# stm32f103vet.net
KiCad netlist of a schematic drawn in EasyEDA
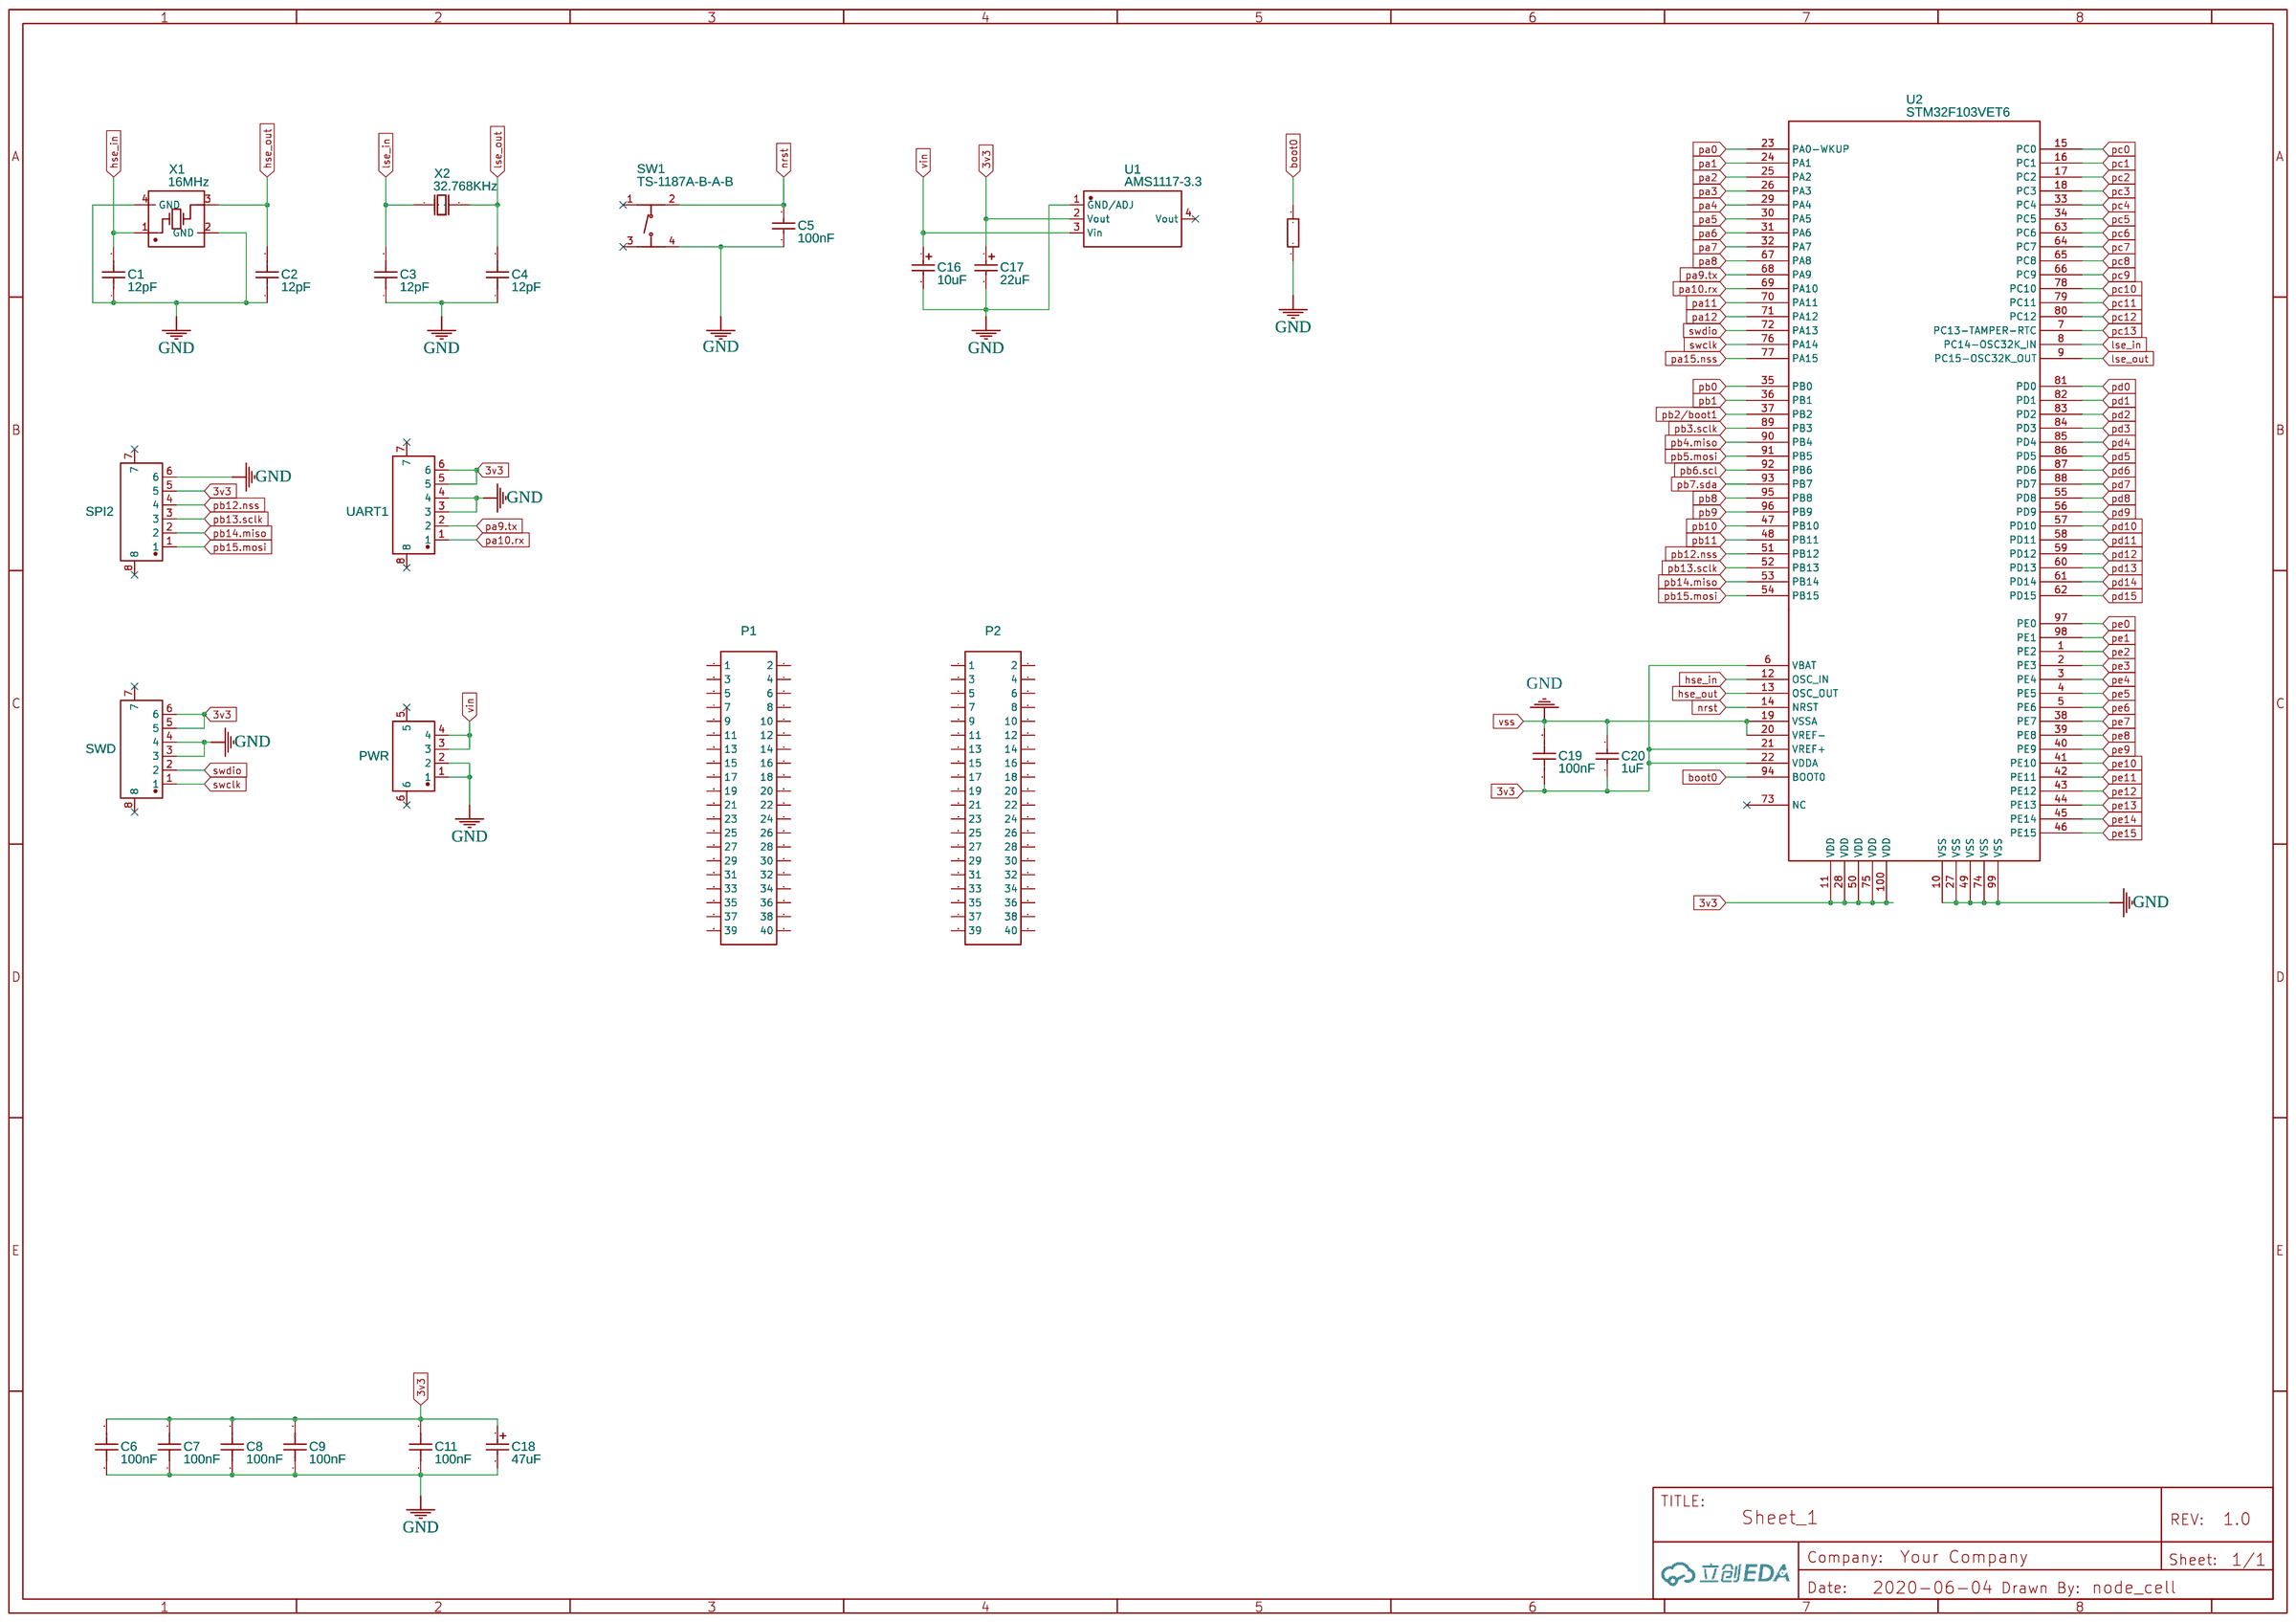
[diagram p0: schematic sheet]

(export (version "E")
  (design (tool "Eeschema 10.0.6"))
  (components
    (comp (ref "C1")
      (value "12pF")
      (fields
        (field (name "BOM_Manufacturer Part") "06035A120K4T2A")
        (field (name "BOM_Supplier Part") "C382067")
      )
      (libsource (lib "") (part "06035A120K4T2A"))
    )
    (comp (ref "C2")
      (value "12pF")
      (fields
        (field (name "BOM_Manufacturer Part") "06035A120K4T2A")
        (field (name "BOM_Supplier Part") "C382067")
      )
      (libsource (lib "") (part "06035A120K4T2A"))
    )
    (comp (ref "C3")
      (value "12pF")
      (fields
        (field (name "BOM_Manufacturer Part") "06035A120K4T2A")
        (field (name "BOM_Supplier Part") "C382067")
      )
      (libsource (lib "") (part "06035A120K4T2A"))
    )
    (comp (ref "C4")
      (value "12pF")
      (fields
        (field (name "BOM_Manufacturer Part") "06035A120K4T2A")
        (field (name "BOM_Supplier Part") "C382067")
      )
      (libsource (lib "") (part "06035A120K4T2A"))
    )
    (comp (ref "C5")
      (value "100nF")
      (fields
        (field (name "BOM_Manufacturer Part") "0603F104M500NT")
        (field (name "BOM_Supplier Part") "C42998")
      )
      (libsource (lib "") (part "0603F104M500NT"))
    )
    (comp (ref "C6")
      (value "100nF")
      (fields
        (field (name "BOM_Manufacturer Part") "C0603X104K050T")
        (field (name "BOM_Supplier Part") "C187860")
      )
      (libsource (lib "") (part "C0603X104K050T"))
    )
    (comp (ref "C7")
      (value "100nF")
      (fields
        (field (name "BOM_Manufacturer Part") "C0603X104K050T")
        (field (name "BOM_Supplier Part") "C187860")
      )
      (libsource (lib "") (part "C0603X104K050T"))
    )
    (comp (ref "C8")
      (value "100nF")
      (fields
        (field (name "BOM_Manufacturer Part") "C0603X104K050T")
        (field (name "BOM_Supplier Part") "C187860")
      )
      (libsource (lib "") (part "C0603X104K050T"))
    )
    (comp (ref "C9")
      (value "100nF")
      (fields
        (field (name "BOM_Manufacturer Part") "C0603X104K050T")
        (field (name "BOM_Supplier Part") "C187860")
      )
      (libsource (lib "") (part "C0603X104K050T"))
    )
    (comp (ref "C11")
      (value "100nF")
      (fields
        (field (name "BOM_Manufacturer Part") "C0603X104K050T")
        (field (name "BOM_Supplier Part") "C187860")
      )
      (libsource (lib "") (part "C0603X104K050T"))
    )
    (comp (ref "C16")
      (value "10uF")
      (fields
        (field (name "BOM_Manufacturer Part") "TAJB106K016RNJ")
        (field (name "BOM_Supplier Part") "C7193")
      )
      (libsource (lib "") (part "TAJB106K016RNJ"))
    )
    (comp (ref "C17")
      (value "22uF")
      (fields
        (field (name "BOM_Manufacturer Part") "TAJB226K016RNJ")
        (field (name "BOM_Supplier Part") "C8020")
      )
      (libsource (lib "") (part "TAJB226K016RNJ"))
    )
    (comp (ref "C18")
      (value "47uF")
      (fields
        (field (name "BOM_Manufacturer Part") "TAJC476K016RNJ")
        (field (name "BOM_Supplier Part") "C7219")
      )
      (libsource (lib "") (part "TAJC476K016RNJ"))
    )
    (comp (ref "C19")
      (value "100nF")
      (fields
        (field (name "BOM_Manufacturer Part") "C0603X104K050T")
        (field (name "BOM_Supplier Part") "C187860")
      )
      (libsource (lib "") (part "C0603X104K050T"))
    )
    (comp (ref "C20")
      (value "1uF")
      (fields
        (field (name "BOM_Manufacturer Part") "CL10A105KA8NNNC")
        (field (name "BOM_Supplier Part") "C5673")
      )
      (libsource (lib "") (part "CL10A105KA8NNNC"))
    )
    (comp (ref "P1")
      (value "Header-Female-2.54_2x20")
      (fields
        (field (name "BOM_Manufacturer Part") "2.54mm 2*20PFemale header")
        (field (name "BOM_Supplier Part") "C50982")
      )
      (libsource (lib "") (part "Header-Female-2.54_2x20"))
    )
    (comp (ref "P2")
      (value "Header-Female-2.54_2x20")
      (fields
        (field (name "BOM_Manufacturer Part") "2.54mm 2*20PFemale header")
        (field (name "BOM_Supplier Part") "C50982")
      )
      (libsource (lib "") (part "Header-Female-2.54_2x20"))
    )
    (comp (ref "PWR")
      (value "AFC10-S04QCC-00")
      (fields (field (name "BOM_Supplier Part") "C395301"))
      (libsource (lib "") (part "AFC10-S04QCC-00"))
    )
    (comp (ref "R2")
      (value "10K")
      (fields
        (field (name "BOM_Manufacturer Part") "0603WAF1002T5E")
        (field (name "BOM_Supplier Part") "C25804")
      )
      (libsource (lib "") (part "0603WAF1002T5E"))
    )
    (comp (ref "SPI2")
      (value "AFC10-S06QCC-00")
      (fields (field (name "BOM_Supplier Part") "C395303"))
      (libsource (lib "") (part "AFC10-S06QCC-00_1"))
    )
    (comp (ref "SW1")
      (value "TS-1187A-B-A-B")
      (fields (field (name "BOM_Supplier Part") "C318884"))
      (libsource (lib "") (part "TS-1187A-B-A-B"))
    )
    (comp (ref "SWD")
      (value "AFC10-S06QCC-00")
      (fields (field (name "BOM_Supplier Part") "C395303"))
      (libsource (lib "") (part "AFC10-S06QCC-00_2"))
    )
    (comp (ref "U1")
      (value "AMS1117-3.3")
      (fields (field (name "BOM_Supplier Part") "C6186"))
      (libsource (lib "") (part "AMS1117-3.3"))
    )
    (comp (ref "U2")
      (value "STM32F103VET6")
      (fields (field (name "BOM_Supplier Part") "C8308"))
      (libsource (lib "") (part "STM32F103VET6"))
    )
    (comp (ref "UART1")
      (value "AFC10-S06QCC-00")
      (fields (field (name "BOM_Supplier Part") "C395303"))
      (libsource (lib "") (part "AFC10-S06QCC-00"))
    )
    (comp (ref "X1")
      (value "16MHz")
      (fields
        (field (name "BOM_Manufacturer Part") "AM16000001")
        (field (name "BOM_Supplier Part") "C409359")
      )
      (libsource (lib "") (part "AM16000001"))
    )
    (comp (ref "X2")
      (value "32.768KHz")
      (fields
        (field (name "BOM_Manufacturer Part") "9H03200028")
        (field (name "BOM_Supplier Part") "C409339")
      )
      (libsource (lib "") (part "9H03200028"))
    )
  )
  (nets
    (net (code "1") (name "3v3") (class "Default")
      (node (ref "C11") (pin "2") (pinfunction "2_2") (pintype "unspecified"))
      (node (ref "C17") (pin "1") (pinfunction "1_1") (pintype "input"))
      (node (ref "C18") (pin "1") (pinfunction "1_1") (pintype "input"))
      (node (ref "C19") (pin "1") (pinfunction "1_1") (pintype "unspecified"))
      (node (ref "C20") (pin "1") (pinfunction "1_1") (pintype "input"))
      (node (ref "C6") (pin "2") (pinfunction "2_2") (pintype "unspecified"))
      (node (ref "C7") (pin "2") (pinfunction "2_2") (pintype "unspecified"))
      (node (ref "C8") (pin "2") (pinfunction "2_2") (pintype "unspecified"))
      (node (ref "C9") (pin "2") (pinfunction "2_2") (pintype "unspecified"))
      (node (ref "SPI2") (pin "5") (pinfunction "5_5") (pintype "unspecified"))
      (node (ref "SWD") (pin "5") (pinfunction "5_5") (pintype "unspecified"))
      (node (ref "SWD") (pin "6") (pinfunction "6_6") (pintype "unspecified"))
      (node (ref "U1") (pin "2") (pinfunction "Vout_2") (pintype "unspecified"))
      (node (ref "U2") (pin "100") (pinfunction "VDD_100") (pintype "unspecified"))
      (node (ref "U2") (pin "11") (pinfunction "VDD_11") (pintype "unspecified"))
      (node (ref "U2") (pin "21") (pinfunction "VREF+_21") (pintype "unspecified"))
      (node (ref "U2") (pin "22") (pinfunction "VDDA_22") (pintype "unspecified"))
      (node (ref "U2") (pin "28") (pinfunction "VDD_28") (pintype "unspecified"))
      (node (ref "U2") (pin "50") (pinfunction "VDD_50") (pintype "unspecified"))
      (node (ref "U2") (pin "6") (pinfunction "VBAT_6") (pintype "unspecified"))
      (node (ref "U2") (pin "75") (pinfunction "VDD_75") (pintype "unspecified"))
      (node (ref "UART1") (pin "5") (pinfunction "5_5") (pintype "unspecified"))
      (node (ref "UART1") (pin "6") (pinfunction "6_6") (pintype "unspecified"))
    )
    (net (code "2") (name "boot0") (class "Default")
      (node (ref "R2") (pin "2") (pinfunction "2_2") (pintype "input"))
      (node (ref "U2") (pin "94") (pinfunction "BOOT0_94") (pintype "unspecified"))
    )
    (net (code "3") (name "hse_in") (class "Default")
      (node (ref "C1") (pin "2") (pinfunction "2_2") (pintype "unspecified"))
      (node (ref "U2") (pin "12") (pinfunction "OSC_IN_12") (pintype "unspecified"))
      (node (ref "X1") (pin "1") (pinfunction "1_1") (pintype "input"))
    )
    (net (code "4") (name "hse_out") (class "Default")
      (node (ref "C2") (pin "2") (pinfunction "2_2") (pintype "unspecified"))
      (node (ref "U2") (pin "13") (pinfunction "OSC_OUT_13") (pintype "unspecified"))
      (node (ref "X1") (pin "3") (pinfunction "3_3") (pintype "input"))
    )
    (net (code "5") (name "lse_in") (class "Default")
      (node (ref "C3") (pin "2") (pinfunction "2_2") (pintype "unspecified"))
      (node (ref "U2") (pin "8") (pinfunction "PC14-OSC32K_IN_8") (pintype "unspecified"))
      (node (ref "X2") (pin "1") (pinfunction "OSC1_1") (pintype "input"))
    )
    (net (code "6") (name "lse_out") (class "Default")
      (node (ref "C4") (pin "2") (pinfunction "2_2") (pintype "unspecified"))
      (node (ref "U2") (pin "9") (pinfunction "PC15-OSC32K_OUT_9") (pintype "unspecified"))
      (node (ref "X2") (pin "2") (pinfunction "OSC2_2") (pintype "input"))
    )
    (net (code "7") (name "nrst") (class "Default")
      (node (ref "C5") (pin "2") (pinfunction "2_2") (pintype "input"))
      (node (ref "SW1") (pin "2") (pinfunction "B_2") (pintype "unspecified"))
      (node (ref "U2") (pin "14") (pinfunction "NRST_14") (pintype "unspecified"))
    )
    (net (code "8") (name "pa0") (class "Default")
      (node (ref "U2") (pin "23") (pinfunction "PA0-WKUP_23") (pintype "unspecified"))
    )
    (net (code "9") (name "pa1") (class "Default")
      (node (ref "U2") (pin "24") (pinfunction "PA1_24") (pintype "unspecified"))
    )
    (net (code "10") (name "pa2") (class "Default")
      (node (ref "U2") (pin "25") (pinfunction "PA2_25") (pintype "unspecified"))
    )
    (net (code "11") (name "pa3") (class "Default")
      (node (ref "U2") (pin "26") (pinfunction "PA3_26") (pintype "unspecified"))
    )
    (net (code "12") (name "pa4") (class "Default")
      (node (ref "U2") (pin "29") (pinfunction "PA4_29") (pintype "unspecified"))
    )
    (net (code "13") (name "pa5") (class "Default")
      (node (ref "U2") (pin "30") (pinfunction "PA5_30") (pintype "unspecified"))
    )
    (net (code "14") (name "pa6") (class "Default")
      (node (ref "U2") (pin "31") (pinfunction "PA6_31") (pintype "unspecified"))
    )
    (net (code "15") (name "pa7") (class "Default")
      (node (ref "U2") (pin "32") (pinfunction "PA7_32") (pintype "unspecified"))
    )
    (net (code "16") (name "pa8") (class "Default")
      (node (ref "U2") (pin "67") (pinfunction "PA8_67") (pintype "unspecified"))
    )
    (net (code "17") (name "pa9.tx") (class "Default")
      (node (ref "U2") (pin "68") (pinfunction "PA9_68") (pintype "unspecified"))
      (node (ref "UART1") (pin "2") (pinfunction "2_2") (pintype "unspecified"))
    )
    (net (code "18") (name "pa10.rx") (class "Default")
      (node (ref "U2") (pin "69") (pinfunction "PA10_69") (pintype "unspecified"))
      (node (ref "UART1") (pin "1") (pinfunction "1_1") (pintype "unspecified"))
    )
    (net (code "19") (name "pa11") (class "Default")
      (node (ref "U2") (pin "70") (pinfunction "PA11_70") (pintype "unspecified"))
    )
    (net (code "20") (name "pa12") (class "Default")
      (node (ref "U2") (pin "71") (pinfunction "PA12_71") (pintype "unspecified"))
    )
    (net (code "21") (name "pa15.nss") (class "Default")
      (node (ref "U2") (pin "77") (pinfunction "PA15_77") (pintype "unspecified"))
    )
    (net (code "22") (name "pb0") (class "Default")
      (node (ref "U2") (pin "35") (pinfunction "PB0_35") (pintype "unspecified"))
    )
    (net (code "23") (name "pb1") (class "Default")
      (node (ref "U2") (pin "36") (pinfunction "PB1_36") (pintype "unspecified"))
    )
    (net (code "24") (name "pb2{slash}boot1") (class "Default")
      (node (ref "U2") (pin "37") (pinfunction "PB2_37") (pintype "unspecified"))
    )
    (net (code "25") (name "pb3.sclk") (class "Default")
      (node (ref "U2") (pin "89") (pinfunction "PB3_89") (pintype "unspecified"))
    )
    (net (code "26") (name "pb4.miso") (class "Default")
      (node (ref "U2") (pin "90") (pinfunction "PB4_90") (pintype "unspecified"))
    )
    (net (code "27") (name "pb5.mosi") (class "Default")
      (node (ref "U2") (pin "91") (pinfunction "PB5_91") (pintype "unspecified"))
    )
    (net (code "28") (name "pb6.scl") (class "Default")
      (node (ref "U2") (pin "92") (pinfunction "PB6_92") (pintype "unspecified"))
    )
    (net (code "29") (name "pb7.sda") (class "Default")
      (node (ref "U2") (pin "93") (pinfunction "PB7_93") (pintype "unspecified"))
    )
    (net (code "30") (name "pb8") (class "Default")
      (node (ref "U2") (pin "95") (pinfunction "PB8_95") (pintype "unspecified"))
    )
    (net (code "31") (name "pb9") (class "Default")
      (node (ref "U2") (pin "96") (pinfunction "PB9_96") (pintype "unspecified"))
    )
    (net (code "32") (name "pb10") (class "Default")
      (node (ref "U2") (pin "47") (pinfunction "PB10_47") (pintype "unspecified"))
    )
    (net (code "33") (name "pb11") (class "Default")
      (node (ref "U2") (pin "48") (pinfunction "PB11_48") (pintype "unspecified"))
    )
    (net (code "34") (name "pb12.nss") (class "Default")
      (node (ref "SPI2") (pin "4") (pinfunction "4_4") (pintype "unspecified"))
      (node (ref "U2") (pin "51") (pinfunction "PB12_51") (pintype "unspecified"))
    )
    (net (code "35") (name "pb13.sclk") (class "Default")
      (node (ref "SPI2") (pin "3") (pinfunction "3_3") (pintype "unspecified"))
      (node (ref "U2") (pin "52") (pinfunction "PB13_52") (pintype "unspecified"))
    )
    (net (code "36") (name "pb14.miso") (class "Default")
      (node (ref "SPI2") (pin "2") (pinfunction "2_2") (pintype "unspecified"))
      (node (ref "U2") (pin "53") (pinfunction "PB14_53") (pintype "unspecified"))
    )
    (net (code "37") (name "pb15.mosi") (class "Default")
      (node (ref "SPI2") (pin "1") (pinfunction "1_1") (pintype "unspecified"))
      (node (ref "U2") (pin "54") (pinfunction "PB15_54") (pintype "unspecified"))
    )
    (net (code "38") (name "pc0") (class "Default")
      (node (ref "U2") (pin "15") (pinfunction "PC0_15") (pintype "unspecified"))
    )
    (net (code "39") (name "pc1") (class "Default")
      (node (ref "U2") (pin "16") (pinfunction "PC1_16") (pintype "unspecified"))
    )
    (net (code "40") (name "pc2") (class "Default")
      (node (ref "U2") (pin "17") (pinfunction "PC2_17") (pintype "unspecified"))
    )
    (net (code "41") (name "pc3") (class "Default")
      (node (ref "U2") (pin "18") (pinfunction "PC3_18") (pintype "unspecified"))
    )
    (net (code "42") (name "pc4") (class "Default")
      (node (ref "U2") (pin "33") (pinfunction "PC4_33") (pintype "unspecified"))
    )
    (net (code "43") (name "pc5") (class "Default")
      (node (ref "U2") (pin "34") (pinfunction "PC5_34") (pintype "unspecified"))
    )
    (net (code "44") (name "pc6") (class "Default")
      (node (ref "U2") (pin "63") (pinfunction "PC6_63") (pintype "unspecified"))
    )
    (net (code "45") (name "pc7") (class "Default")
      (node (ref "U2") (pin "64") (pinfunction "PC7_64") (pintype "unspecified"))
    )
    (net (code "46") (name "pc8") (class "Default")
      (node (ref "U2") (pin "65") (pinfunction "PC8_65") (pintype "unspecified"))
    )
    (net (code "47") (name "pc9") (class "Default")
      (node (ref "U2") (pin "66") (pinfunction "PC9_66") (pintype "unspecified"))
    )
    (net (code "48") (name "pc10") (class "Default")
      (node (ref "U2") (pin "78") (pinfunction "PC10_78") (pintype "unspecified"))
    )
    (net (code "49") (name "pc11") (class "Default")
      (node (ref "U2") (pin "79") (pinfunction "PC11_79") (pintype "unspecified"))
    )
    (net (code "50") (name "pc12") (class "Default")
      (node (ref "U2") (pin "80") (pinfunction "PC12_80") (pintype "unspecified"))
    )
    (net (code "51") (name "pc13") (class "Default")
      (node (ref "U2") (pin "7") (pinfunction "PC13-TAMPER-RTC_7") (pintype "unspecified"))
    )
    (net (code "52") (name "pd0") (class "Default")
      (node (ref "U2") (pin "81") (pinfunction "PD0_81") (pintype "unspecified"))
    )
    (net (code "53") (name "pd1") (class "Default")
      (node (ref "U2") (pin "82") (pinfunction "PD1_82") (pintype "unspecified"))
    )
    (net (code "54") (name "pd2") (class "Default")
      (node (ref "U2") (pin "83") (pinfunction "PD2_83") (pintype "unspecified"))
    )
    (net (code "55") (name "pd3") (class "Default")
      (node (ref "U2") (pin "84") (pinfunction "PD3_84") (pintype "unspecified"))
    )
    (net (code "56") (name "pd4") (class "Default")
      (node (ref "U2") (pin "85") (pinfunction "PD4_85") (pintype "unspecified"))
    )
    (net (code "57") (name "pd5") (class "Default")
      (node (ref "U2") (pin "86") (pinfunction "PD5_86") (pintype "unspecified"))
    )
    (net (code "58") (name "pd6") (class "Default")
      (node (ref "U2") (pin "87") (pinfunction "PD6_87") (pintype "unspecified"))
    )
    (net (code "59") (name "pd7") (class "Default")
      (node (ref "U2") (pin "88") (pinfunction "PD7_88") (pintype "unspecified"))
    )
    (net (code "60") (name "pd8") (class "Default")
      (node (ref "U2") (pin "55") (pinfunction "PD8_55") (pintype "unspecified"))
    )
    (net (code "61") (name "pd9") (class "Default")
      (node (ref "U2") (pin "56") (pinfunction "PD9_56") (pintype "unspecified"))
    )
    (net (code "62") (name "pd10") (class "Default")
      (node (ref "U2") (pin "57") (pinfunction "PD10_57") (pintype "unspecified"))
    )
    (net (code "63") (name "pd11") (class "Default")
      (node (ref "U2") (pin "58") (pinfunction "PD11_58") (pintype "unspecified"))
    )
    (net (code "64") (name "pd12") (class "Default")
      (node (ref "U2") (pin "59") (pinfunction "PD12_59") (pintype "unspecified"))
    )
    (net (code "65") (name "pd13") (class "Default")
      (node (ref "U2") (pin "60") (pinfunction "PD13_60") (pintype "unspecified"))
    )
    (net (code "66") (name "pd14") (class "Default")
      (node (ref "U2") (pin "61") (pinfunction "PD14_61") (pintype "unspecified"))
    )
    (net (code "67") (name "pd15") (class "Default")
      (node (ref "U2") (pin "62") (pinfunction "PD15_62") (pintype "unspecified"))
    )
    (net (code "68") (name "pe0") (class "Default")
      (node (ref "U2") (pin "97") (pinfunction "PE0_97") (pintype "unspecified"))
    )
    (net (code "69") (name "pe1") (class "Default")
      (node (ref "U2") (pin "98") (pinfunction "PE1_98") (pintype "unspecified"))
    )
    (net (code "70") (name "pe2") (class "Default")
      (node (ref "U2") (pin "1") (pinfunction "PE2_1") (pintype "unspecified"))
    )
    (net (code "71") (name "pe3") (class "Default")
      (node (ref "U2") (pin "2") (pinfunction "PE3_2") (pintype "unspecified"))
    )
    (net (code "72") (name "pe4") (class "Default")
      (node (ref "U2") (pin "3") (pinfunction "PE4_3") (pintype "unspecified"))
    )
    (net (code "73") (name "pe5") (class "Default")
      (node (ref "U2") (pin "4") (pinfunction "PE5_4") (pintype "unspecified"))
    )
    (net (code "74") (name "pe6") (class "Default")
      (node (ref "U2") (pin "5") (pinfunction "PE6_5") (pintype "unspecified"))
    )
    (net (code "75") (name "pe7") (class "Default")
      (node (ref "U2") (pin "38") (pinfunction "PE7_38") (pintype "unspecified"))
    )
    (net (code "76") (name "pe8") (class "Default")
      (node (ref "U2") (pin "39") (pinfunction "PE8_39") (pintype "unspecified"))
    )
    (net (code "77") (name "pe9") (class "Default")
      (node (ref "U2") (pin "40") (pinfunction "PE9_40") (pintype "unspecified"))
    )
    (net (code "78") (name "pe10") (class "Default")
      (node (ref "U2") (pin "41") (pinfunction "PE10_41") (pintype "unspecified"))
    )
    (net (code "79") (name "pe11") (class "Default")
      (node (ref "U2") (pin "42") (pinfunction "PE11_42") (pintype "unspecified"))
    )
    (net (code "80") (name "pe12") (class "Default")
      (node (ref "U2") (pin "43") (pinfunction "PE12_43") (pintype "unspecified"))
    )
    (net (code "81") (name "pe13") (class "Default")
      (node (ref "U2") (pin "44") (pinfunction "PE13_44") (pintype "unspecified"))
    )
    (net (code "82") (name "pe14") (class "Default")
      (node (ref "U2") (pin "45") (pinfunction "PE14_45") (pintype "unspecified"))
    )
    (net (code "83") (name "pe15") (class "Default")
      (node (ref "U2") (pin "46") (pinfunction "PE15_46") (pintype "unspecified"))
    )
    (net (code "84") (name "swclk") (class "Default")
      (node (ref "SWD") (pin "1") (pinfunction "1_1") (pintype "unspecified"))
      (node (ref "U2") (pin "76") (pinfunction "PA14_76") (pintype "unspecified"))
    )
    (net (code "85") (name "swdio") (class "Default")
      (node (ref "SWD") (pin "2") (pinfunction "2_2") (pintype "unspecified"))
      (node (ref "U2") (pin "72") (pinfunction "PA13_72") (pintype "unspecified"))
    )
    (net (code "86") (name "unconnected-(P1-Pad1)") (class "Default")
      (node (ref "P1") (pin "1") (pinfunction "1_1") (pintype "input"))
    )
    (net (code "87") (name "unconnected-(P1-Pad2)") (class "Default")
      (node (ref "P1") (pin "2") (pinfunction "2_2") (pintype "input"))
    )
    (net (code "88") (name "unconnected-(P1-Pad3)") (class "Default")
      (node (ref "P1") (pin "3") (pinfunction "3_3") (pintype "input"))
    )
    (net (code "89") (name "unconnected-(P1-Pad4)") (class "Default")
      (node (ref "P1") (pin "4") (pinfunction "4_4") (pintype "input"))
    )
    (net (code "90") (name "unconnected-(P1-Pad5)") (class "Default")
      (node (ref "P1") (pin "5") (pinfunction "5_5") (pintype "input"))
    )
    (net (code "91") (name "unconnected-(P1-Pad6)") (class "Default")
      (node (ref "P1") (pin "6") (pinfunction "6_6") (pintype "input"))
    )
    (net (code "92") (name "unconnected-(P1-Pad7)") (class "Default")
      (node (ref "P1") (pin "7") (pinfunction "7_7") (pintype "input"))
    )
    (net (code "93") (name "unconnected-(P1-Pad8)") (class "Default")
      (node (ref "P1") (pin "8") (pinfunction "8_8") (pintype "input"))
    )
    (net (code "94") (name "unconnected-(P1-Pad9)") (class "Default")
      (node (ref "P1") (pin "9") (pinfunction "9_9") (pintype "input"))
    )
    (net (code "95") (name "unconnected-(P1-Pad10)") (class "Default")
      (node (ref "P1") (pin "10") (pinfunction "10_10") (pintype "input"))
    )
    (net (code "96") (name "unconnected-(P1-Pad11)") (class "Default")
      (node (ref "P1") (pin "11") (pinfunction "11_11") (pintype "input"))
    )
    (net (code "97") (name "unconnected-(P1-Pad12)") (class "Default")
      (node (ref "P1") (pin "12") (pinfunction "12_12") (pintype "input"))
    )
    (net (code "98") (name "unconnected-(P1-Pad13)") (class "Default")
      (node (ref "P1") (pin "13") (pinfunction "13_13") (pintype "input"))
    )
    (net (code "99") (name "unconnected-(P1-Pad14)") (class "Default")
      (node (ref "P1") (pin "14") (pinfunction "14_14") (pintype "input"))
    )
    (net (code "100") (name "unconnected-(P1-Pad15)") (class "Default")
      (node (ref "P1") (pin "15") (pinfunction "15_15") (pintype "input"))
    )
    (net (code "101") (name "unconnected-(P1-Pad16)") (class "Default")
      (node (ref "P1") (pin "16") (pinfunction "16_16") (pintype "input"))
    )
    (net (code "102") (name "unconnected-(P1-Pad17)") (class "Default")
      (node (ref "P1") (pin "17") (pinfunction "17_17") (pintype "input"))
    )
    (net (code "103") (name "unconnected-(P1-Pad18)") (class "Default")
      (node (ref "P1") (pin "18") (pinfunction "18_18") (pintype "input"))
    )
    (net (code "104") (name "unconnected-(P1-Pad19)") (class "Default")
      (node (ref "P1") (pin "19") (pinfunction "19_19") (pintype "input"))
    )
    (net (code "105") (name "unconnected-(P1-Pad20)") (class "Default")
      (node (ref "P1") (pin "20") (pinfunction "20_20") (pintype "input"))
    )
    (net (code "106") (name "unconnected-(P1-Pad21)") (class "Default")
      (node (ref "P1") (pin "21") (pinfunction "21_21") (pintype "input"))
    )
    (net (code "107") (name "unconnected-(P1-Pad22)") (class "Default")
      (node (ref "P1") (pin "22") (pinfunction "22_22") (pintype "input"))
    )
    (net (code "108") (name "unconnected-(P1-Pad23)") (class "Default")
      (node (ref "P1") (pin "23") (pinfunction "23_23") (pintype "input"))
    )
    (net (code "109") (name "unconnected-(P1-Pad24)") (class "Default")
      (node (ref "P1") (pin "24") (pinfunction "24_24") (pintype "input"))
    )
    (net (code "110") (name "unconnected-(P1-Pad25)") (class "Default")
      (node (ref "P1") (pin "25") (pinfunction "25_25") (pintype "input"))
    )
    (net (code "111") (name "unconnected-(P1-Pad26)") (class "Default")
      (node (ref "P1") (pin "26") (pinfunction "26_26") (pintype "input"))
    )
    (net (code "112") (name "unconnected-(P1-Pad27)") (class "Default")
      (node (ref "P1") (pin "27") (pinfunction "27_27") (pintype "input"))
    )
    (net (code "113") (name "unconnected-(P1-Pad28)") (class "Default")
      (node (ref "P1") (pin "28") (pinfunction "28_28") (pintype "input"))
    )
    (net (code "114") (name "unconnected-(P1-Pad29)") (class "Default")
      (node (ref "P1") (pin "29") (pinfunction "29_29") (pintype "input"))
    )
    (net (code "115") (name "unconnected-(P1-Pad30)") (class "Default")
      (node (ref "P1") (pin "30") (pinfunction "30_30") (pintype "input"))
    )
    (net (code "116") (name "unconnected-(P1-Pad31)") (class "Default")
      (node (ref "P1") (pin "31") (pinfunction "31_31") (pintype "input"))
    )
    (net (code "117") (name "unconnected-(P1-Pad32)") (class "Default")
      (node (ref "P1") (pin "32") (pinfunction "32_32") (pintype "input"))
    )
    (net (code "118") (name "unconnected-(P1-Pad33)") (class "Default")
      (node (ref "P1") (pin "33") (pinfunction "33_33") (pintype "input"))
    )
    (net (code "119") (name "unconnected-(P1-Pad34)") (class "Default")
      (node (ref "P1") (pin "34") (pinfunction "34_34") (pintype "input"))
    )
    (net (code "120") (name "unconnected-(P1-Pad35)") (class "Default")
      (node (ref "P1") (pin "35") (pinfunction "35_35") (pintype "input"))
    )
    (net (code "121") (name "unconnected-(P1-Pad36)") (class "Default")
      (node (ref "P1") (pin "36") (pinfunction "36_36") (pintype "input"))
    )
    (net (code "122") (name "unconnected-(P1-Pad37)") (class "Default")
      (node (ref "P1") (pin "37") (pinfunction "37_37") (pintype "input"))
    )
    (net (code "123") (name "unconnected-(P1-Pad38)") (class "Default")
      (node (ref "P1") (pin "38") (pinfunction "38_38") (pintype "input"))
    )
    (net (code "124") (name "unconnected-(P1-Pad39)") (class "Default")
      (node (ref "P1") (pin "39") (pinfunction "39_39") (pintype "input"))
    )
    (net (code "125") (name "unconnected-(P1-Pad40)") (class "Default")
      (node (ref "P1") (pin "40") (pinfunction "40_40") (pintype "input"))
    )
    (net (code "126") (name "unconnected-(P2-Pad1)") (class "Default")
      (node (ref "P2") (pin "1") (pinfunction "1_1") (pintype "input"))
    )
    (net (code "127") (name "unconnected-(P2-Pad2)") (class "Default")
      (node (ref "P2") (pin "2") (pinfunction "2_2") (pintype "input"))
    )
    (net (code "128") (name "unconnected-(P2-Pad3)") (class "Default")
      (node (ref "P2") (pin "3") (pinfunction "3_3") (pintype "input"))
    )
    (net (code "129") (name "unconnected-(P2-Pad4)") (class "Default")
      (node (ref "P2") (pin "4") (pinfunction "4_4") (pintype "input"))
    )
    (net (code "130") (name "unconnected-(P2-Pad5)") (class "Default")
      (node (ref "P2") (pin "5") (pinfunction "5_5") (pintype "input"))
    )
    (net (code "131") (name "unconnected-(P2-Pad6)") (class "Default")
      (node (ref "P2") (pin "6") (pinfunction "6_6") (pintype "input"))
    )
    (net (code "132") (name "unconnected-(P2-Pad7)") (class "Default")
      (node (ref "P2") (pin "7") (pinfunction "7_7") (pintype "input"))
    )
    (net (code "133") (name "unconnected-(P2-Pad8)") (class "Default")
      (node (ref "P2") (pin "8") (pinfunction "8_8") (pintype "input"))
    )
    (net (code "134") (name "unconnected-(P2-Pad9)") (class "Default")
      (node (ref "P2") (pin "9") (pinfunction "9_9") (pintype "input"))
    )
    (net (code "135") (name "unconnected-(P2-Pad10)") (class "Default")
      (node (ref "P2") (pin "10") (pinfunction "10_10") (pintype "input"))
    )
    (net (code "136") (name "unconnected-(P2-Pad11)") (class "Default")
      (node (ref "P2") (pin "11") (pinfunction "11_11") (pintype "input"))
    )
    (net (code "137") (name "unconnected-(P2-Pad12)") (class "Default")
      (node (ref "P2") (pin "12") (pinfunction "12_12") (pintype "input"))
    )
    (net (code "138") (name "unconnected-(P2-Pad13)") (class "Default")
      (node (ref "P2") (pin "13") (pinfunction "13_13") (pintype "input"))
    )
    (net (code "139") (name "unconnected-(P2-Pad14)") (class "Default")
      (node (ref "P2") (pin "14") (pinfunction "14_14") (pintype "input"))
    )
    (net (code "140") (name "unconnected-(P2-Pad15)") (class "Default")
      (node (ref "P2") (pin "15") (pinfunction "15_15") (pintype "input"))
    )
    (net (code "141") (name "unconnected-(P2-Pad16)") (class "Default")
      (node (ref "P2") (pin "16") (pinfunction "16_16") (pintype "input"))
    )
    (net (code "142") (name "unconnected-(P2-Pad17)") (class "Default")
      (node (ref "P2") (pin "17") (pinfunction "17_17") (pintype "input"))
    )
    (net (code "143") (name "unconnected-(P2-Pad18)") (class "Default")
      (node (ref "P2") (pin "18") (pinfunction "18_18") (pintype "input"))
    )
    (net (code "144") (name "unconnected-(P2-Pad19)") (class "Default")
      (node (ref "P2") (pin "19") (pinfunction "19_19") (pintype "input"))
    )
    (net (code "145") (name "unconnected-(P2-Pad20)") (class "Default")
      (node (ref "P2") (pin "20") (pinfunction "20_20") (pintype "input"))
    )
    (net (code "146") (name "unconnected-(P2-Pad21)") (class "Default")
      (node (ref "P2") (pin "21") (pinfunction "21_21") (pintype "input"))
    )
    (net (code "147") (name "unconnected-(P2-Pad22)") (class "Default")
      (node (ref "P2") (pin "22") (pinfunction "22_22") (pintype "input"))
    )
    (net (code "148") (name "unconnected-(P2-Pad23)") (class "Default")
      (node (ref "P2") (pin "23") (pinfunction "23_23") (pintype "input"))
    )
    (net (code "149") (name "unconnected-(P2-Pad24)") (class "Default")
      (node (ref "P2") (pin "24") (pinfunction "24_24") (pintype "input"))
    )
    (net (code "150") (name "unconnected-(P2-Pad25)") (class "Default")
      (node (ref "P2") (pin "25") (pinfunction "25_25") (pintype "input"))
    )
    (net (code "151") (name "unconnected-(P2-Pad26)") (class "Default")
      (node (ref "P2") (pin "26") (pinfunction "26_26") (pintype "input"))
    )
    (net (code "152") (name "unconnected-(P2-Pad27)") (class "Default")
      (node (ref "P2") (pin "27") (pinfunction "27_27") (pintype "input"))
    )
    (net (code "153") (name "unconnected-(P2-Pad28)") (class "Default")
      (node (ref "P2") (pin "28") (pinfunction "28_28") (pintype "input"))
    )
    (net (code "154") (name "unconnected-(P2-Pad29)") (class "Default")
      (node (ref "P2") (pin "29") (pinfunction "29_29") (pintype "input"))
    )
    (net (code "155") (name "unconnected-(P2-Pad30)") (class "Default")
      (node (ref "P2") (pin "30") (pinfunction "30_30") (pintype "input"))
    )
    (net (code "156") (name "unconnected-(P2-Pad31)") (class "Default")
      (node (ref "P2") (pin "31") (pinfunction "31_31") (pintype "input"))
    )
    (net (code "157") (name "unconnected-(P2-Pad32)") (class "Default")
      (node (ref "P2") (pin "32") (pinfunction "32_32") (pintype "input"))
    )
    (net (code "158") (name "unconnected-(P2-Pad33)") (class "Default")
      (node (ref "P2") (pin "33") (pinfunction "33_33") (pintype "input"))
    )
    (net (code "159") (name "unconnected-(P2-Pad34)") (class "Default")
      (node (ref "P2") (pin "34") (pinfunction "34_34") (pintype "input"))
    )
    (net (code "160") (name "unconnected-(P2-Pad35)") (class "Default")
      (node (ref "P2") (pin "35") (pinfunction "35_35") (pintype "input"))
    )
    (net (code "161") (name "unconnected-(P2-Pad36)") (class "Default")
      (node (ref "P2") (pin "36") (pinfunction "36_36") (pintype "input"))
    )
    (net (code "162") (name "unconnected-(P2-Pad37)") (class "Default")
      (node (ref "P2") (pin "37") (pinfunction "37_37") (pintype "input"))
    )
    (net (code "163") (name "unconnected-(P2-Pad38)") (class "Default")
      (node (ref "P2") (pin "38") (pinfunction "38_38") (pintype "input"))
    )
    (net (code "164") (name "unconnected-(P2-Pad39)") (class "Default")
      (node (ref "P2") (pin "39") (pinfunction "39_39") (pintype "input"))
    )
    (net (code "165") (name "unconnected-(P2-Pad40)") (class "Default")
      (node (ref "P2") (pin "40") (pinfunction "40_40") (pintype "input"))
    )
    (net (code "166") (name "unconnected-(PWR-Pad5)") (class "Default")
      (node (ref "PWR") (pin "5") (pinfunction "5_5") (pintype "unspecified+no_connect"))
    )
    (net (code "167") (name "unconnected-(PWR-Pad6)") (class "Default")
      (node (ref "PWR") (pin "6") (pinfunction "6_6") (pintype "unspecified+no_connect"))
    )
    (net (code "168") (name "unconnected-(SPI2-Pad7)") (class "Default")
      (node (ref "SPI2") (pin "7") (pinfunction "7_7") (pintype "unspecified+no_connect"))
    )
    (net (code "169") (name "unconnected-(SPI2-Pad8)") (class "Default")
      (node (ref "SPI2") (pin "8") (pinfunction "8_8") (pintype "unspecified+no_connect"))
    )
    (net (code "170") (name "unconnected-(SW1-A-Pad1)") (class "Default")
      (node (ref "SW1") (pin "1") (pinfunction "A_1") (pintype "unspecified+no_connect"))
    )
    (net (code "171") (name "unconnected-(SW1-C-Pad3)") (class "Default")
      (node (ref "SW1") (pin "3") (pinfunction "C_3") (pintype "unspecified+no_connect"))
    )
    (net (code "172") (name "unconnected-(SWD-Pad7)") (class "Default")
      (node (ref "SWD") (pin "7") (pinfunction "7_7") (pintype "unspecified+no_connect"))
    )
    (net (code "173") (name "unconnected-(SWD-Pad8)") (class "Default")
      (node (ref "SWD") (pin "8") (pinfunction "8_8") (pintype "unspecified+no_connect"))
    )
    (net (code "174") (name "unconnected-(U1-Vout-Pad4)") (class "Default")
      (node (ref "U1") (pin "4") (pinfunction "Vout_4") (pintype "unspecified+no_connect"))
    )
    (net (code "175") (name "unconnected-(U2-NC-Pad73)") (class "Default")
      (node (ref "U2") (pin "73") (pinfunction "NC_73") (pintype "unspecified+no_connect"))
    )
    (net (code "176") (name "unconnected-(UART1-Pad7)") (class "Default")
      (node (ref "UART1") (pin "7") (pinfunction "7_7") (pintype "unspecified+no_connect"))
    )
    (net (code "177") (name "unconnected-(UART1-Pad8)") (class "Default")
      (node (ref "UART1") (pin "8") (pinfunction "8_8") (pintype "unspecified+no_connect"))
    )
    (net (code "178") (name "vin") (class "Default")
      (node (ref "C16") (pin "1") (pinfunction "1_1") (pintype "input"))
      (node (ref "PWR") (pin "3") (pinfunction "3_3") (pintype "unspecified"))
      (node (ref "PWR") (pin "4") (pinfunction "4_4") (pintype "unspecified"))
      (node (ref "U1") (pin "3") (pinfunction "Vin_3") (pintype "unspecified"))
    )
    (net (code "179") (name "vss") (class "Default")
      (node (ref "C1") (pin "1") (pinfunction "1_1") (pintype "unspecified"))
      (node (ref "C11") (pin "1") (pinfunction "1_1") (pintype "unspecified"))
      (node (ref "C16") (pin "2") (pinfunction "2_2") (pintype "input"))
      (node (ref "C17") (pin "2") (pinfunction "2_2") (pintype "input"))
      (node (ref "C18") (pin "2") (pinfunction "2_2") (pintype "input"))
      (node (ref "C19") (pin "2") (pinfunction "2_2") (pintype "unspecified"))
      (node (ref "C2") (pin "1") (pinfunction "1_1") (pintype "unspecified"))
      (node (ref "C20") (pin "2") (pinfunction "2_2") (pintype "input"))
      (node (ref "C3") (pin "1") (pinfunction "1_1") (pintype "unspecified"))
      (node (ref "C4") (pin "1") (pinfunction "1_1") (pintype "unspecified"))
      (node (ref "C5") (pin "1") (pinfunction "1_1") (pintype "input"))
      (node (ref "C6") (pin "1") (pinfunction "1_1") (pintype "unspecified"))
      (node (ref "C7") (pin "1") (pinfunction "1_1") (pintype "unspecified"))
      (node (ref "C8") (pin "1") (pinfunction "1_1") (pintype "unspecified"))
      (node (ref "C9") (pin "1") (pinfunction "1_1") (pintype "unspecified"))
      (node (ref "PWR") (pin "1") (pinfunction "1_1") (pintype "unspecified"))
      (node (ref "PWR") (pin "2") (pinfunction "2_2") (pintype "unspecified"))
      (node (ref "R2") (pin "1") (pinfunction "1_1") (pintype "input"))
      (node (ref "SPI2") (pin "6") (pinfunction "6_6") (pintype "unspecified"))
      (node (ref "SW1") (pin "4") (pinfunction "D_4") (pintype "unspecified"))
      (node (ref "SWD") (pin "3") (pinfunction "3_3") (pintype "unspecified"))
      (node (ref "SWD") (pin "4") (pinfunction "4_4") (pintype "unspecified"))
      (node (ref "U1") (pin "1") (pinfunction "GND/ADJ_1") (pintype "unspecified"))
      (node (ref "U2") (pin "10") (pinfunction "VSS_10") (pintype "unspecified"))
      (node (ref "U2") (pin "19") (pinfunction "VSSA_19") (pintype "unspecified"))
      (node (ref "U2") (pin "20") (pinfunction "VREF-_20") (pintype "unspecified"))
      (node (ref "U2") (pin "27") (pinfunction "VSS_27") (pintype "unspecified"))
      (node (ref "U2") (pin "49") (pinfunction "VSS_49") (pintype "unspecified"))
      (node (ref "U2") (pin "74") (pinfunction "VSS_74") (pintype "unspecified"))
      (node (ref "U2") (pin "99") (pinfunction "VSS_99") (pintype "unspecified"))
      (node (ref "UART1") (pin "3") (pinfunction "3_3") (pintype "unspecified"))
      (node (ref "UART1") (pin "4") (pinfunction "4_4") (pintype "unspecified"))
      (node (ref "X1") (pin "2") (pinfunction "GND_2") (pintype "input"))
      (node (ref "X1") (pin "4") (pinfunction "GND_4") (pintype "input"))
    )
  )
)
